# esp_energy.net
KiCad netlist of a schematic drawn in EAGLE
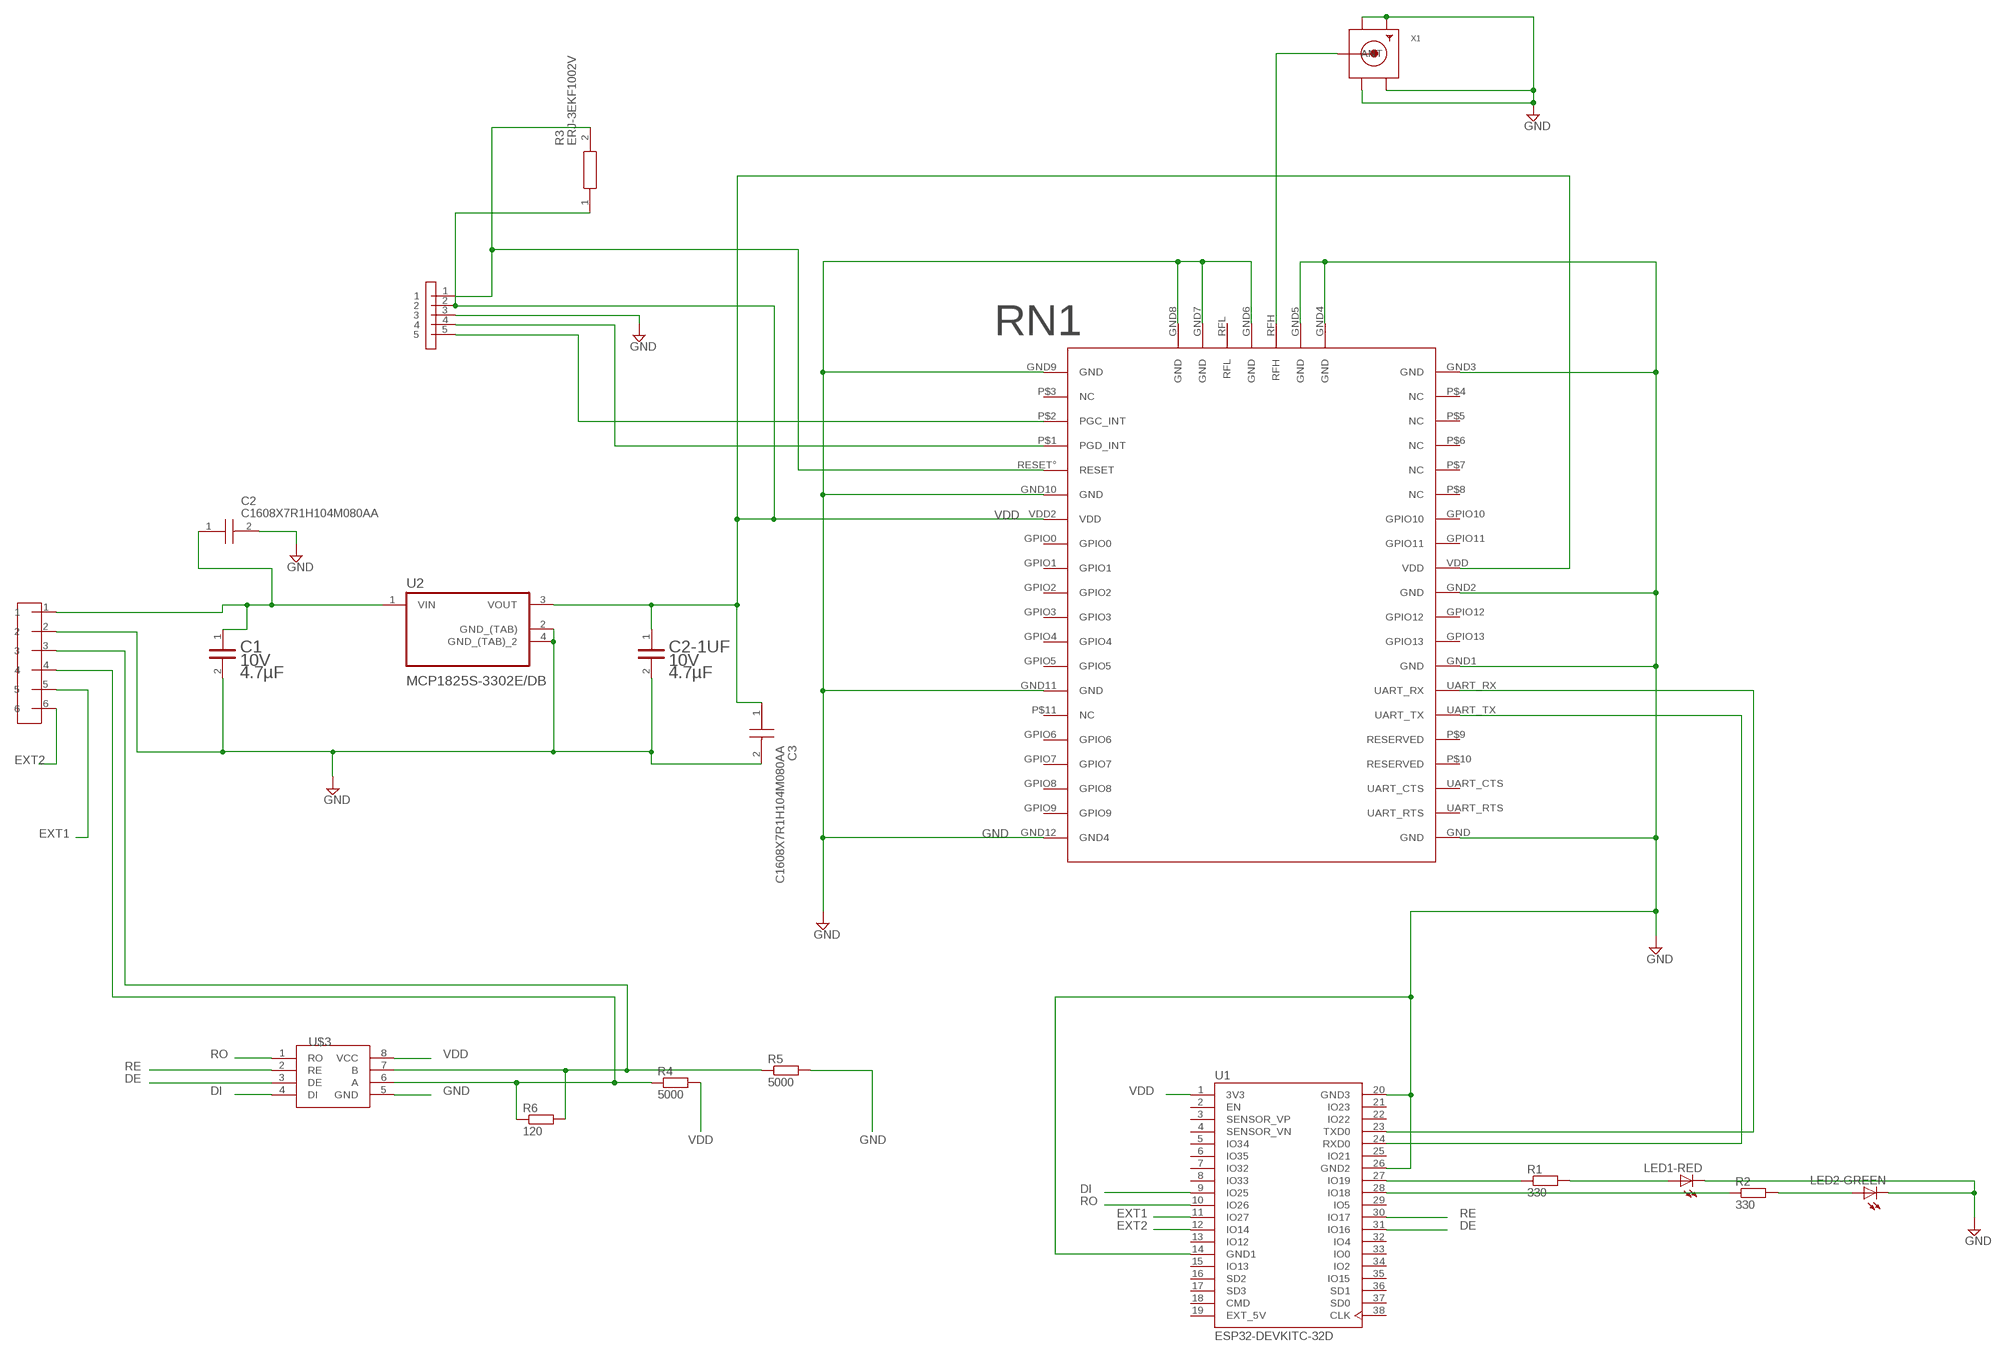
[diagram p0: schematic, sheet 1]

(export (version "E")
  (design (tool "Eeschema 10.0.6"))
  (components
    (comp (ref "C1")
      (value "KEMET_C0603C475K8PACTUKEMET_C0603C475K8PACTU_0_0")
      (footprint "eagle-import:KEMET_C0603C475K8PACTU_0")
      (fields
        (field (name "DIGIKEY_PART_NUMBER") "399-5503-1-ND")
        (field (name "MF") "Kemet")
        (field (name "MOUSER_PART_NUMBER") "80-C0603C475K8P")
      )
      (libsource (lib "eagle-import") (part "KEMET_C0603C475K8PACTUKEMET_C0603C475K8PACTU_0_0"))
    )
    (comp (ref "C2")
      (value "C1608X7R1H104M080AA")
      (footprint "eagle-import:CAPC1608X80N")
      (fields (field (name "MOUSER_PART_NUMBER") "810-C1608X7R1H104M"))
      (libsource (lib "eagle-import") (part "C1608X7R1H104M080AA"))
    )
    (comp (ref "C2-1UF")
      (value "KEMET_C0603C475K8PACTUKEMET_C0603C475K8PACTU_0_0")
      (footprint "eagle-import:KEMET_C0603C475K8PACTU_0")
      (fields
        (field (name "DIGIKEY_PART_NUMBER") "399-5503-1-ND")
        (field (name "MF") "Kemet")
        (field (name "MOUSER_PART_NUMBER") "80-C0603C475K8P")
      )
      (libsource (lib "eagle-import") (part "KEMET_C0603C475K8PACTUKEMET_C0603C475K8PACTU_0_0"))
    )
    (comp (ref "C3")
      (value "C1608X7R1H104M080AA")
      (footprint "eagle-import:CAPC1608X80N")
      (fields (field (name "MOUSER_PART_NUMBER") "810-C1608X7R1H104M"))
      (libsource (lib "eagle-import") (part "C1608X7R1H104M080AA"))
    )
    (comp (ref "LED1-RED")
      (value "LEDCHIP-LED0603")
      (footprint "eagle-import:CHIP-LED0603")
      (libsource (lib "eagle-import") (part "LEDCHIP-LED0603"))
    )
    (comp (ref "LED2-GREEN")
      (value "LEDCHIP-LED0603")
      (footprint "eagle-import:CHIP-LED0603")
      (libsource (lib "eagle-import") (part "LEDCHIP-LED0603"))
    )
    (comp (ref "R1")
      (value "330")
      (footprint "eagle-import:R0603")
      (libsource (lib "eagle-import") (part "R-EU_R0603"))
    )
    (comp (ref "R2")
      (value "330")
      (footprint "eagle-import:R0603")
      (libsource (lib "eagle-import") (part "R-EU_R0603"))
    )
    (comp (ref "R3")
      (value "ERJ-3EKF1002V")
      (footprint "eagle-import:RESC1608X55N")
      (fields (field (name "MOUSER_PART_NUMBER") "667-ERJ-3EKF1002V"))
      (libsource (lib "eagle-import") (part "ERJ-3EKF1002V"))
    )
    (comp (ref "R4")
      (value "5000")
      (footprint "eagle-import:R0805")
      (libsource (lib "eagle-import") (part "R-EU_R0805"))
    )
    (comp (ref "R5")
      (value "5000")
      (footprint "eagle-import:R0805")
      (libsource (lib "eagle-import") (part "R-EU_R0805"))
    )
    (comp (ref "R6")
      (value "120")
      (footprint "eagle-import:R0805")
      (libsource (lib "eagle-import") (part "R-EU_R0805"))
    )
    (comp (ref "RN1")
      (value "NEW_RN2483")
      (footprint "eagle-import:NEW_RN2483")
      (libsource (lib "eagle-import") (part "NEW_RN2483"))
    )
    (comp (ref "U$1")
      (value "CONNECTOR62")
      (footprint "eagle-import:CONNECTOR6")
      (libsource (lib "eagle-import") (part "CONNECTOR62"))
    )
    (comp (ref "U$2")
      (value "ICSP52")
      (footprint "eagle-import:ICSP")
      (libsource (lib "eagle-import") (part "ICSP52"))
    )
    (comp (ref "U$3")
      (value "AMD3485E")
      (footprint "eagle-import:AMD3485E")
      (libsource (lib "eagle-import") (part "AMD3485E"))
    )
    (comp (ref "U1")
      (value "ESP32-DEVKITC-32D")
      (footprint "eagle-import:MODULE_ESP32-DEVKITC-32D")
      (fields (field (name "MF") "Espressif Systems"))
      (libsource (lib "eagle-import") (part "ESP32-DEVKITC-32D"))
    )
    (comp (ref "U2")
      (value "MCP1825S-3302E/DB")
      (footprint "eagle-import:SOT230P700X180-4N")
      (fields (field (name "MF") "Microchip"))
      (libsource (lib "eagle-import") (part "MCP1825S-3302E/DB"))
    )
    (comp (ref "X1")
      (value "SMACONNECTOR_EDGE")
      (footprint "eagle-import:SMA_EDGELAUNCH")
      (libsource (lib "eagle-import") (part "SMACONNECTOR_EDGE"))
    )
  )
  (nets
    (net (code "1") (name "/DE") (class "Default")
      (node (ref "U$3") (pin "3") (pinfunction "DE_3") (pintype "bidirectional"))
      (node (ref "U1") (pin "31") (pinfunction "IO16_31") (pintype "bidirectional"))
    )
    (net (code "2") (name "/DI") (class "Default")
      (node (ref "U$3") (pin "4") (pinfunction "DI_4") (pintype "bidirectional"))
      (node (ref "U1") (pin "9") (pinfunction "IO25_9") (pintype "bidirectional"))
    )
    (net (code "3") (name "/EXT1") (class "Default")
      (node (ref "U$1") (pin "5") (pinfunction "5_5") (pintype "bidirectional"))
      (node (ref "U1") (pin "11") (pinfunction "IO27_11") (pintype "bidirectional"))
    )
    (net (code "4") (name "/EXT2") (class "Default")
      (node (ref "U$1") (pin "6") (pinfunction "6_6") (pintype "bidirectional"))
      (node (ref "U1") (pin "12") (pinfunction "IO14_12") (pintype "bidirectional"))
    )
    (net (code "5") (name "/EXT_5V") (class "Default")
      (node (ref "U1") (pin "19") (pinfunction "EXT_5V_19") (pintype "power_in"))
    )
    (net (code "6") (name "/RE") (class "Default")
      (node (ref "U$3") (pin "2") (pinfunction "RE_2") (pintype "bidirectional"))
      (node (ref "U1") (pin "30") (pinfunction "IO17_30") (pintype "bidirectional"))
    )
    (net (code "7") (name "/RO") (class "Default")
      (node (ref "U$3") (pin "1") (pinfunction "RO_1") (pintype "bidirectional"))
      (node (ref "U1") (pin "10") (pinfunction "IO26_10") (pintype "bidirectional"))
    )
    (net (code "8") (name "/VDD") (class "Default")
      (node (ref "C2-1UF") (pin "1") (pinfunction "1_1") (pintype "bidirectional"))
      (node (ref "C3") (pin "1") (pinfunction "1_1") (pintype "bidirectional"))
      (node (ref "R3") (pin "1") (pinfunction "1_1") (pintype "bidirectional"))
      (node (ref "R4") (pin "2") (pinfunction "2_2") (pintype "passive"))
      (node (ref "RN1") (pin "VDD") (pinfunction "VDD_VDD") (pintype "bidirectional"))
      (node (ref "RN1") (pin "VDD2") (pinfunction "VDD_VDD2") (pintype "bidirectional"))
      (node (ref "U$2") (pin "2") (pinfunction "2_2") (pintype "bidirectional"))
      (node (ref "U$3") (pin "8") (pinfunction "VCC_8") (pintype "bidirectional"))
      (node (ref "U1") (pin "1") (pinfunction "3V3_1") (pintype "power_in"))
      (node (ref "U2") (pin "3") (pinfunction "VOUT_3") (pintype "output"))
    )
    (net (code "9") (name "GND") (class "Default")
      (node (ref "C1") (pin "2") (pinfunction "2_2") (pintype "bidirectional"))
      (node (ref "C2") (pin "2") (pinfunction "2_2") (pintype "bidirectional"))
      (node (ref "C2-1UF") (pin "2") (pinfunction "2_2") (pintype "bidirectional"))
      (node (ref "C3") (pin "2") (pinfunction "2_2") (pintype "bidirectional"))
      (node (ref "LED1-RED") (pin "C") (pinfunction "C_C") (pintype "passive"))
      (node (ref "LED2-GREEN") (pin "C") (pinfunction "C_C") (pintype "passive"))
      (node (ref "R5") (pin "2") (pinfunction "2_2") (pintype "passive"))
      (node (ref "RN1") (pin "GND") (pinfunction "GND_GND") (pintype "bidirectional"))
      (node (ref "RN1") (pin "GND1") (pinfunction "GND_GND1") (pintype "bidirectional"))
      (node (ref "RN1") (pin "GND10") (pinfunction "GND_GND10") (pintype "bidirectional"))
      (node (ref "RN1") (pin "GND11") (pinfunction "GND_GND11") (pintype "bidirectional"))
      (node (ref "RN1") (pin "GND12") (pinfunction "GND4_GND12") (pintype "bidirectional"))
      (node (ref "RN1") (pin "GND2") (pinfunction "GND_GND2") (pintype "bidirectional"))
      (node (ref "RN1") (pin "GND3") (pinfunction "GND_GND3") (pintype "bidirectional"))
      (node (ref "RN1") (pin "GND4") (pinfunction "GND_GND4") (pintype "bidirectional"))
      (node (ref "RN1") (pin "GND5") (pinfunction "GND_GND5") (pintype "bidirectional"))
      (node (ref "RN1") (pin "GND6") (pinfunction "GND_GND6") (pintype "bidirectional"))
      (node (ref "RN1") (pin "GND7") (pinfunction "GND_GND7") (pintype "bidirectional"))
      (node (ref "RN1") (pin "GND8") (pinfunction "GND_GND8") (pintype "bidirectional"))
      (node (ref "RN1") (pin "GND9") (pinfunction "GND_GND9") (pintype "bidirectional"))
      (node (ref "U$1") (pin "2") (pinfunction "2_2") (pintype "bidirectional"))
      (node (ref "U$2") (pin "3") (pinfunction "3_3") (pintype "bidirectional"))
      (node (ref "U$3") (pin "5") (pinfunction "GND_5") (pintype "bidirectional"))
      (node (ref "U1") (pin "14") (pinfunction "GND1_14") (pintype "power_in"))
      (node (ref "U1") (pin "20") (pinfunction "GND3_20") (pintype "power_in"))
      (node (ref "U1") (pin "26") (pinfunction "GND2_26") (pintype "power_in"))
      (node (ref "U2") (pin "2") (pinfunction "GND_(TAB)_2") (pintype "power_in"))
      (node (ref "U2") (pin "4") (pinfunction "GND_(TAB)_2_4") (pintype "power_in"))
      (node (ref "X1") (pin "GND@1") (pinfunction "GND4_GND@1") (pintype "power_in"))
      (node (ref "X1") (pin "GND@2") (pinfunction "GND3_GND@2") (pintype "power_in"))
      (node (ref "X1") (pin "GND@3") (pinfunction "GND2_GND@3") (pintype "power_in"))
      (node (ref "X1") (pin "GND@4") (pinfunction "GND1_GND@4") (pintype "power_in"))
    )
    (net (code "10") (name "Net-(LED1-RED-PadA)") (class "Default")
      (node (ref "LED1-RED") (pin "A") (pinfunction "A_A") (pintype "passive"))
      (node (ref "R1") (pin "2") (pinfunction "2_2") (pintype "passive"))
    )
    (net (code "11") (name "Net-(LED2-GREEN-PadA)") (class "Default")
      (node (ref "LED2-GREEN") (pin "A") (pinfunction "A_A") (pintype "passive"))
      (node (ref "R2") (pin "2") (pinfunction "2_2") (pintype "passive"))
    )
    (net (code "12") (name "Net-(RN1-PGC_INT)") (class "Default")
      (node (ref "RN1") (pin "P$2") (pinfunction "PGC_INT_P$2") (pintype "bidirectional"))
      (node (ref "U$2") (pin "5") (pinfunction "5_5") (pintype "bidirectional"))
    )
    (net (code "13") (name "Net-(RN1-PGD_INT)") (class "Default")
      (node (ref "RN1") (pin "P$1") (pinfunction "PGD_INT_P$1") (pintype "bidirectional"))
      (node (ref "U$2") (pin "4") (pinfunction "4_4") (pintype "bidirectional"))
    )
    (net (code "14") (name "Net-(RN1-RESET)") (class "Default")
      (node (ref "R3") (pin "2") (pinfunction "2_2") (pintype "bidirectional"))
      (node (ref "RN1") (pin "RESET°") (pinfunction "RESET_RESET°") (pintype "bidirectional"))
      (node (ref "U$2") (pin "1") (pinfunction "1_1") (pintype "bidirectional"))
    )
    (net (code "15") (name "Net-(U$3-A)") (class "Default")
      (node (ref "R4") (pin "1") (pinfunction "1_1") (pintype "passive"))
      (node (ref "R6") (pin "1") (pinfunction "1_1") (pintype "passive"))
      (node (ref "U$1") (pin "4") (pinfunction "4_4") (pintype "bidirectional"))
      (node (ref "U$3") (pin "6") (pinfunction "A_6") (pintype "bidirectional"))
    )
    (net (code "16") (name "Net-(U$3-B)") (class "Default")
      (node (ref "R5") (pin "1") (pinfunction "1_1") (pintype "passive"))
      (node (ref "R6") (pin "2") (pinfunction "2_2") (pintype "passive"))
      (node (ref "U$1") (pin "3") (pinfunction "3_3") (pintype "bidirectional"))
      (node (ref "U$3") (pin "7") (pinfunction "B_7") (pintype "bidirectional"))
    )
    (net (code "17") (name "Net-(U1-IO18)") (class "Default")
      (node (ref "R2") (pin "1") (pinfunction "1_1") (pintype "passive"))
      (node (ref "U1") (pin "28") (pinfunction "IO18_28") (pintype "bidirectional"))
    )
    (net (code "18") (name "Net-(U1-IO19)") (class "Default")
      (node (ref "R1") (pin "1") (pinfunction "1_1") (pintype "passive"))
      (node (ref "U1") (pin "27") (pinfunction "IO19_27") (pintype "bidirectional"))
    )
    (net (code "19") (name "Net-(U1-RXD0)") (class "Default")
      (node (ref "RN1") (pin "UART_TX") (pinfunction "UART_TX_UART_TX") (pintype "bidirectional"))
      (node (ref "U1") (pin "24") (pinfunction "RXD0_24") (pintype "input"))
    )
    (net (code "20") (name "Net-(U1-TXD0)") (class "Default")
      (node (ref "RN1") (pin "UART_RX") (pinfunction "UART_RX_UART_RX") (pintype "bidirectional"))
      (node (ref "U1") (pin "23") (pinfunction "TXD0_23") (pintype "output"))
    )
    (net (code "21") (name "Net-(U2-VIN)") (class "Default")
      (node (ref "C1") (pin "1") (pinfunction "1_1") (pintype "bidirectional"))
      (node (ref "C2") (pin "1") (pinfunction "1_1") (pintype "bidirectional"))
      (node (ref "U$1") (pin "1") (pinfunction "1_1") (pintype "bidirectional"))
      (node (ref "U2") (pin "1") (pinfunction "VIN_1") (pintype "input"))
    )
    (net (code "22") (name "Net-(X1-ANT)") (class "Default")
      (node (ref "RN1") (pin "RFH") (pinfunction "RFH_RFH") (pintype "bidirectional"))
      (node (ref "X1") (pin "P") (pinfunction "ANT_P") (pintype "bidirectional"))
    )
    (net (code "23") (name "unconnected-(RN1-NC-PadP$3)") (class "Default")
      (node (ref "RN1") (pin "P$3") (pinfunction "NC_P$3") (pintype "bidirectional"))
    )
    (net (code "24") (name "unconnected-(RN1-NC-PadP$4)") (class "Default")
      (node (ref "RN1") (pin "P$4") (pinfunction "NC_P$4") (pintype "bidirectional"))
    )
    (net (code "25") (name "unconnected-(RN1-NC-PadP$5)") (class "Default")
      (node (ref "RN1") (pin "P$5") (pinfunction "NC_P$5") (pintype "bidirectional"))
    )
    (net (code "26") (name "unconnected-(RN1-NC-PadP$6)") (class "Default")
      (node (ref "RN1") (pin "P$6") (pinfunction "NC_P$6") (pintype "bidirectional"))
    )
    (net (code "27") (name "unconnected-(RN1-NC-PadP$7)") (class "Default")
      (node (ref "RN1") (pin "P$7") (pinfunction "NC_P$7") (pintype "bidirectional"))
    )
    (net (code "28") (name "unconnected-(RN1-NC-PadP$8)") (class "Default")
      (node (ref "RN1") (pin "P$8") (pinfunction "NC_P$8") (pintype "bidirectional"))
    )
    (net (code "29") (name "unconnected-(RN1-NC-PadP$11)") (class "Default")
      (node (ref "RN1") (pin "P$11") (pinfunction "NC_P$11") (pintype "bidirectional"))
    )
    (net (code "30") (name "unconnected-(RN1-PadGPIO0)") (class "Default")
      (node (ref "RN1") (pin "GPIO0") (pinfunction "GPIO0_GPIO0") (pintype "bidirectional"))
    )
    (net (code "31") (name "unconnected-(RN1-PadGPIO1)") (class "Default")
      (node (ref "RN1") (pin "GPIO1") (pinfunction "GPIO1_GPIO1") (pintype "bidirectional"))
    )
    (net (code "32") (name "unconnected-(RN1-PadGPIO2)") (class "Default")
      (node (ref "RN1") (pin "GPIO2") (pinfunction "GPIO2_GPIO2") (pintype "bidirectional"))
    )
    (net (code "33") (name "unconnected-(RN1-PadGPIO3)") (class "Default")
      (node (ref "RN1") (pin "GPIO3") (pinfunction "GPIO3_GPIO3") (pintype "bidirectional"))
    )
    (net (code "34") (name "unconnected-(RN1-PadGPIO4)") (class "Default")
      (node (ref "RN1") (pin "GPIO4") (pinfunction "GPIO4_GPIO4") (pintype "bidirectional"))
    )
    (net (code "35") (name "unconnected-(RN1-PadGPIO5)") (class "Default")
      (node (ref "RN1") (pin "GPIO5") (pinfunction "GPIO5_GPIO5") (pintype "bidirectional"))
    )
    (net (code "36") (name "unconnected-(RN1-PadGPIO6)") (class "Default")
      (node (ref "RN1") (pin "GPIO6") (pinfunction "GPIO6_GPIO6") (pintype "bidirectional"))
    )
    (net (code "37") (name "unconnected-(RN1-PadGPIO7)") (class "Default")
      (node (ref "RN1") (pin "GPIO7") (pinfunction "GPIO7_GPIO7") (pintype "bidirectional"))
    )
    (net (code "38") (name "unconnected-(RN1-PadGPIO8)") (class "Default")
      (node (ref "RN1") (pin "GPIO8") (pinfunction "GPIO8_GPIO8") (pintype "bidirectional"))
    )
    (net (code "39") (name "unconnected-(RN1-PadGPIO9)") (class "Default")
      (node (ref "RN1") (pin "GPIO9") (pinfunction "GPIO9_GPIO9") (pintype "bidirectional"))
    )
    (net (code "40") (name "unconnected-(RN1-PadGPIO10)") (class "Default")
      (node (ref "RN1") (pin "GPIO10") (pinfunction "GPIO10_GPIO10") (pintype "bidirectional"))
    )
    (net (code "41") (name "unconnected-(RN1-PadGPIO11)") (class "Default")
      (node (ref "RN1") (pin "GPIO11") (pinfunction "GPIO11_GPIO11") (pintype "bidirectional"))
    )
    (net (code "42") (name "unconnected-(RN1-PadGPIO12)") (class "Default")
      (node (ref "RN1") (pin "GPIO12") (pinfunction "GPIO12_GPIO12") (pintype "bidirectional"))
    )
    (net (code "43") (name "unconnected-(RN1-PadGPIO13)") (class "Default")
      (node (ref "RN1") (pin "GPIO13") (pinfunction "GPIO13_GPIO13") (pintype "bidirectional"))
    )
    (net (code "44") (name "unconnected-(RN1-PadRFL)") (class "Default")
      (node (ref "RN1") (pin "RFL") (pinfunction "RFL_RFL") (pintype "bidirectional"))
    )
    (net (code "45") (name "unconnected-(RN1-PadUART_CTS)") (class "Default")
      (node (ref "RN1") (pin "UART_CTS") (pinfunction "UART_CTS_UART_CTS") (pintype "bidirectional"))
    )
    (net (code "46") (name "unconnected-(RN1-PadUART_RTS)") (class "Default")
      (node (ref "RN1") (pin "UART_RTS") (pinfunction "UART_RTS_UART_RTS") (pintype "bidirectional"))
    )
    (net (code "47") (name "unconnected-(RN1-RESERVED-PadP$9)") (class "Default")
      (node (ref "RN1") (pin "P$9") (pinfunction "RESERVED_P$9") (pintype "bidirectional"))
    )
    (net (code "48") (name "unconnected-(RN1-RESERVED-PadP$10)") (class "Default")
      (node (ref "RN1") (pin "P$10") (pinfunction "RESERVED_P$10") (pintype "bidirectional"))
    )
    (net (code "49") (name "unconnected-(U1-CLK-Pad38)") (class "Default")
      (node (ref "U1") (pin "38") (pinfunction "CLK_38") (pintype "input"))
    )
    (net (code "50") (name "unconnected-(U1-CMD-Pad18)") (class "Default")
      (node (ref "U1") (pin "18") (pinfunction "CMD_18") (pintype "bidirectional"))
    )
    (net (code "51") (name "unconnected-(U1-EN-Pad2)") (class "Default")
      (node (ref "U1") (pin "2") (pinfunction "EN_2") (pintype "input"))
    )
    (net (code "52") (name "unconnected-(U1-IO0-Pad33)") (class "Default")
      (node (ref "U1") (pin "33") (pinfunction "IO0_33") (pintype "bidirectional"))
    )
    (net (code "53") (name "unconnected-(U1-IO2-Pad34)") (class "Default")
      (node (ref "U1") (pin "34") (pinfunction "IO2_34") (pintype "bidirectional"))
    )
    (net (code "54") (name "unconnected-(U1-IO4-Pad32)") (class "Default")
      (node (ref "U1") (pin "32") (pinfunction "IO4_32") (pintype "bidirectional"))
    )
    (net (code "55") (name "unconnected-(U1-IO5-Pad29)") (class "Default")
      (node (ref "U1") (pin "29") (pinfunction "IO5_29") (pintype "bidirectional"))
    )
    (net (code "56") (name "unconnected-(U1-IO12-Pad13)") (class "Default")
      (node (ref "U1") (pin "13") (pinfunction "IO12_13") (pintype "bidirectional"))
    )
    (net (code "57") (name "unconnected-(U1-IO13-Pad15)") (class "Default")
      (node (ref "U1") (pin "15") (pinfunction "IO13_15") (pintype "bidirectional"))
    )
    (net (code "58") (name "unconnected-(U1-IO15-Pad35)") (class "Default")
      (node (ref "U1") (pin "35") (pinfunction "IO15_35") (pintype "bidirectional"))
    )
    (net (code "59") (name "unconnected-(U1-IO21-Pad25)") (class "Default")
      (node (ref "U1") (pin "25") (pinfunction "IO21_25") (pintype "bidirectional"))
    )
    (net (code "60") (name "unconnected-(U1-IO22-Pad22)") (class "Default")
      (node (ref "U1") (pin "22") (pinfunction "IO22_22") (pintype "bidirectional"))
    )
    (net (code "61") (name "unconnected-(U1-IO23-Pad21)") (class "Default")
      (node (ref "U1") (pin "21") (pinfunction "IO23_21") (pintype "bidirectional"))
    )
    (net (code "62") (name "unconnected-(U1-IO32-Pad7)") (class "Default")
      (node (ref "U1") (pin "7") (pinfunction "IO32_7") (pintype "bidirectional"))
    )
    (net (code "63") (name "unconnected-(U1-IO33-Pad8)") (class "Default")
      (node (ref "U1") (pin "8") (pinfunction "IO33_8") (pintype "bidirectional"))
    )
    (net (code "64") (name "unconnected-(U1-IO34-Pad5)") (class "Default")
      (node (ref "U1") (pin "5") (pinfunction "IO34_5") (pintype "bidirectional"))
    )
    (net (code "65") (name "unconnected-(U1-IO35-Pad6)") (class "Default")
      (node (ref "U1") (pin "6") (pinfunction "IO35_6") (pintype "bidirectional"))
    )
    (net (code "66") (name "unconnected-(U1-SD0-Pad37)") (class "Default")
      (node (ref "U1") (pin "37") (pinfunction "SD0_37") (pintype "bidirectional"))
    )
    (net (code "67") (name "unconnected-(U1-SD1-Pad36)") (class "Default")
      (node (ref "U1") (pin "36") (pinfunction "SD1_36") (pintype "bidirectional"))
    )
    (net (code "68") (name "unconnected-(U1-SD2-Pad16)") (class "Default")
      (node (ref "U1") (pin "16") (pinfunction "SD2_16") (pintype "bidirectional"))
    )
    (net (code "69") (name "unconnected-(U1-SD3-Pad17)") (class "Default")
      (node (ref "U1") (pin "17") (pinfunction "SD3_17") (pintype "bidirectional"))
    )
    (net (code "70") (name "unconnected-(U1-SENSOR_VN-Pad4)") (class "Default")
      (node (ref "U1") (pin "4") (pinfunction "SENSOR_VN_4") (pintype "input"))
    )
    (net (code "71") (name "unconnected-(U1-SENSOR_VP-Pad3)") (class "Default")
      (node (ref "U1") (pin "3") (pinfunction "SENSOR_VP_3") (pintype "input"))
    )
  )
)
